# Sensor_RPM.net
KiCad netlist of a schematic drawn in EAGLE
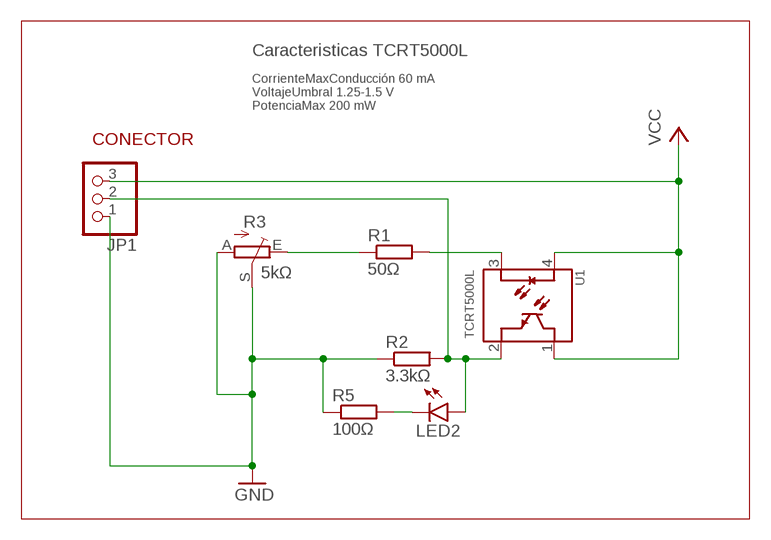
[diagram p0: schematic, sheet 1]

(export (version "E")
  (design (tool "Eeschema 10.0.6"))
  (components
    (comp (ref "JP1")
      (value "PINHD-1X3")
      (footprint "eagle-import:1X03")
      (fields (field (name "PARTNO") "PPPC031LFBN-RC"))
      (libsource (lib "eagle-import") (part "PINHD-1X3"))
    )
    (comp (ref "LED2")
      (value "LEDCHIP-LED0805")
      (footprint "eagle-import:CHIP-LED0805")
      (fields (field (name "PARTNO") "EAST2012GA0"))
      (libsource (lib "eagle-import") (part "LEDCHIP-LED0805"))
    )
    (comp (ref "R1")
      (value "50Ω")
      (footprint "eagle-import:R0805")
      (fields (field (name "PARTNO") "RT0805FRE0751RL"))
      (libsource (lib "eagle-import") (part "R-EU_R0805"))
    )
    (comp (ref "R2")
      (value "3.3kΩ")
      (footprint "eagle-import:R0805")
      (fields (field (name "PARTNO") "RC0402FR-073K3L"))
      (libsource (lib "eagle-import") (part "R-EU_R0805"))
    )
    (comp (ref "R3")
      (value "5kΩ")
      (footprint "eagle-import:CT6")
      (fields (field (name "PARTNO") "CT-6EP502"))
      (libsource (lib "eagle-import") (part "TRIM_EU-CT6"))
    )
    (comp (ref "R5")
      (value "100Ω")
      (footprint "eagle-import:R0805")
      (fields (field (name "PARTNO") "RC0805FR-07100RL"))
      (libsource (lib "eagle-import") (part "R-EU_R0805"))
    )
    (comp (ref "U1")
      (value "TCRT5000L")
      (footprint "eagle-import:PCBMOUNT")
      (fields (field (name "MF") "Vishay"))
      (libsource (lib "eagle-import") (part "TCRT5000L"))
    )
  )
  (nets
    (net (code "1") (name "GND") (class "Default")
      (node (ref "JP1") (pin "1") (pinfunction "1_1") (pintype "passive"))
      (node (ref "R2") (pin "1") (pinfunction "1_1") (pintype "passive"))
      (node (ref "R3") (pin "A") (pinfunction "A_A") (pintype "passive"))
      (node (ref "R3") (pin "S") (pinfunction "S_S") (pintype "passive"))
      (node (ref "R5") (pin "1") (pinfunction "1_1") (pintype "passive"))
    )
    (net (code "2") (name "Net-(LED2-PadC)") (class "Default")
      (node (ref "LED2") (pin "C") (pinfunction "C_C") (pintype "passive"))
      (node (ref "R5") (pin "2") (pinfunction "2_2") (pintype "passive"))
    )
    (net (code "3") (name "Net-(R1-Pad1)") (class "Default")
      (node (ref "R1") (pin "1") (pinfunction "1_1") (pintype "passive"))
      (node (ref "R3") (pin "E") (pinfunction "E_E") (pintype "passive"))
    )
    (net (code "4") (name "Net-(U1-C)") (class "Default")
      (node (ref "R1") (pin "2") (pinfunction "2_2") (pintype "passive"))
      (node (ref "U1") (pin "3") (pinfunction "C_3") (pintype "passive"))
    )
    (net (code "5") (name "Net-(U1-E)") (class "Default")
      (node (ref "JP1") (pin "2") (pinfunction "2_2") (pintype "passive"))
      (node (ref "LED2") (pin "A") (pinfunction "A_A") (pintype "passive"))
      (node (ref "R2") (pin "2") (pinfunction "2_2") (pintype "passive"))
      (node (ref "U1") (pin "2") (pinfunction "E_2") (pintype "passive"))
    )
    (net (code "6") (name "VCC") (class "Default")
      (node (ref "JP1") (pin "3") (pinfunction "3_3") (pintype "passive"))
      (node (ref "U1") (pin "1") (pinfunction "CO_1") (pintype "passive"))
      (node (ref "U1") (pin "4") (pinfunction "A_4") (pintype "passive"))
    )
  )
)
